# NFC__2021-03-03.net
KiCad netlist of a schematic drawn in EasyEDA
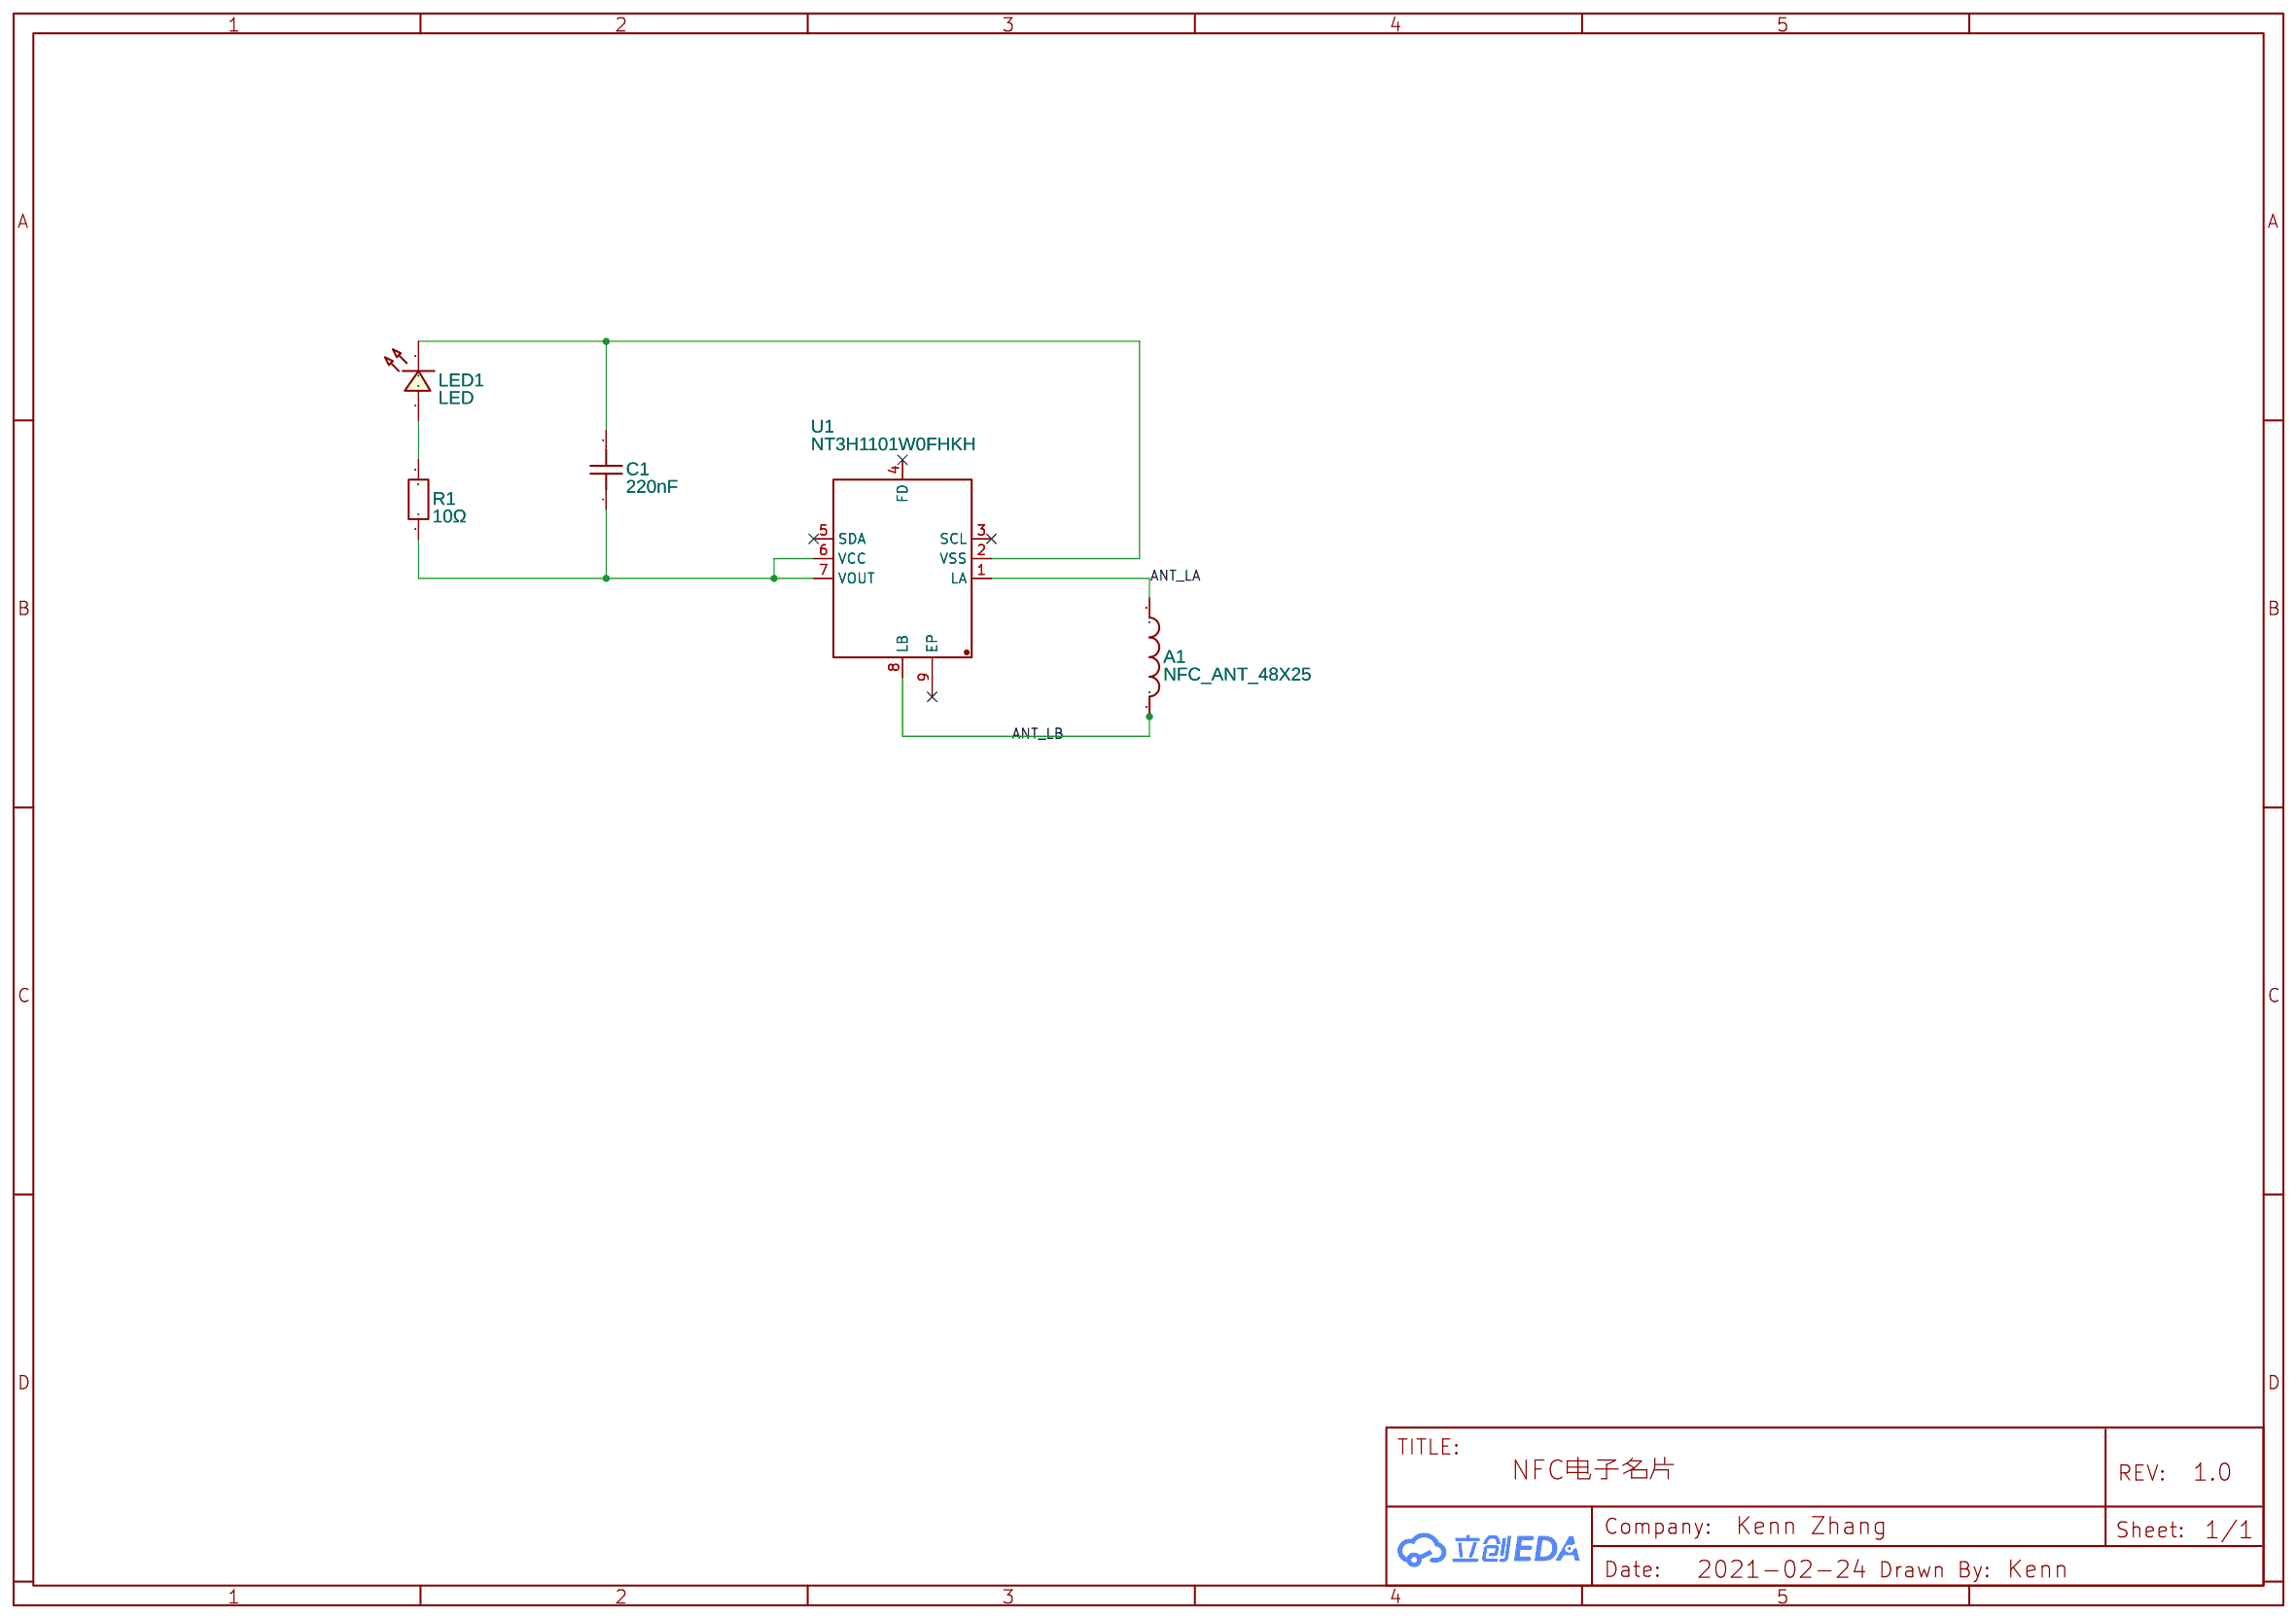
[diagram p0: schematic sheet]

(export (version "E")
  (design (tool "Eeschema 10.0.6"))
  (components
    (comp (ref "A1") (value "NFC_ANT_48X25") (libsource (lib "") (part "NFC_ANT_48X25")))
    (comp (ref "C1")
      (value "220nF")
      (fields
        (field (name "BOM_Manufacturer Part") "0603B224K160CT")
        (field (name "BOM_Supplier Part") "C338153")
      )
      (libsource (lib "") (part "C_0603_US"))
    )
    (comp (ref "LED1")
      (value "LED")
      (fields (field (name "BOM_Manufacturer Part") "NCD0603G2") (field (name "BOM_Supplier Part") "C87326"))
      (libsource (lib "") (part "LED-0603_R"))
    )
    (comp (ref "R1")
      (value "10Ω")
      (fields
        (field (name "BOM_Manufacturer Part") "0603WAF100JT5E")
        (field (name "BOM_Supplier Part") "C22859")
      )
      (libsource (lib "") (part "R_0603_EU"))
    )
    (comp (ref "U1")
      (value "NT3H1101W0FHKH")
      (fields (field (name "BOM_Supplier Part") "C73156"))
      (libsource (lib "") (part "NT3H1101W0FHKH"))
    )
  )
  (nets
    (net (code "1") (name "/ANT_LA") (class "Default")
      (node (ref "A1") (pin "A") (pinfunction "A_A") (pintype "bidirectional"))
      (node (ref "U1") (pin "1") (pinfunction "LA_1") (pintype "unspecified"))
    )
    (net (code "2") (name "/ANT_LB") (class "Default")
      (node (ref "A1") (pin "B") (pinfunction "B_B") (pintype "bidirectional"))
      (node (ref "A1") (pin "P$3") (pinfunction "B_P$3") (pintype "bidirectional"))
      (node (ref "U1") (pin "8") (pinfunction "LB_8") (pintype "unspecified"))
    )
    (net (code "3") (name "Net-(LED1-Pad1)") (class "Default")
      (node (ref "LED1") (pin "1") (pinfunction "1_1") (pintype "unspecified"))
      (node (ref "R1") (pin "2") (pinfunction "2_2") (pintype "unspecified"))
    )
    (net (code "4") (name "Net-(U1-VCC)") (class "Default")
      (node (ref "C1") (pin "1") (pinfunction "1_1") (pintype "unspecified"))
      (node (ref "R1") (pin "1") (pinfunction "1_1") (pintype "unspecified"))
      (node (ref "U1") (pin "6") (pinfunction "VCC_6") (pintype "unspecified"))
      (node (ref "U1") (pin "7") (pinfunction "VOUT_7") (pintype "unspecified"))
    )
    (net (code "5") (name "Net-(U1-VSS)") (class "Default")
      (node (ref "C1") (pin "2") (pinfunction "2_2") (pintype "unspecified"))
      (node (ref "LED1") (pin "2") (pinfunction "2_2") (pintype "unspecified"))
      (node (ref "U1") (pin "2") (pinfunction "VSS_2") (pintype "unspecified"))
    )
    (net (code "6") (name "unconnected-(U1-EP-Pad9)") (class "Default")
      (node (ref "U1") (pin "9") (pinfunction "EP_9") (pintype "unspecified+no_connect"))
    )
    (net (code "7") (name "unconnected-(U1-FD-Pad4)") (class "Default")
      (node (ref "U1") (pin "4") (pinfunction "FD_4") (pintype "unspecified+no_connect"))
    )
    (net (code "8") (name "unconnected-(U1-SCL-Pad3)") (class "Default")
      (node (ref "U1") (pin "3") (pinfunction "SCL_3") (pintype "unspecified+no_connect"))
    )
    (net (code "9") (name "unconnected-(U1-SDA-Pad5)") (class "Default")
      (node (ref "U1") (pin "5") (pinfunction "SDA_5") (pintype "unspecified+no_connect"))
    )
  )
)
